# Hall_Effect_Sensor.net
KiCad netlist of a schematic drawn in EAGLE
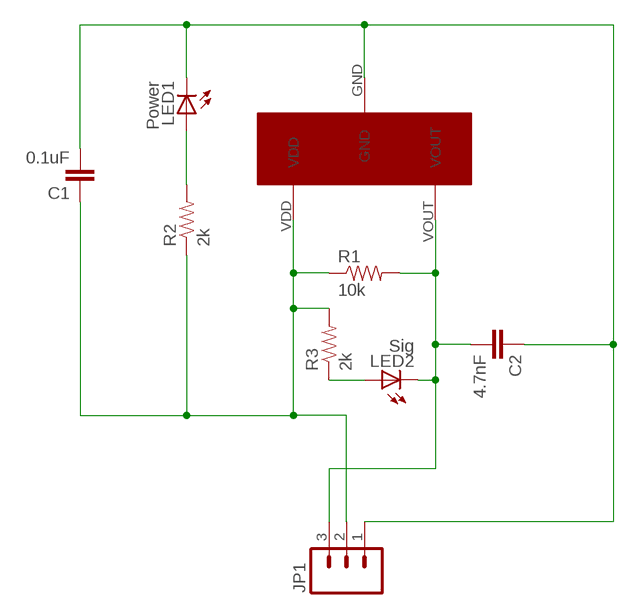
[diagram p0: schematic, sheet 1]

(export (version "E")
  (design (tool "Eeschema 10.0.6"))
  (components
    (comp (ref "C1")
      (value "0.1uF")
      (footprint "eagle-import:0603-CAP")
      (libsource (lib "eagle-import") (part "CAP0603-CAP"))
    )
    (comp (ref "C2")
      (value "4.7nF")
      (footprint "eagle-import:0603-CAP")
      (libsource (lib "eagle-import") (part "CAP0603-CAP"))
    )
    (comp (ref "JP1")
      (value "M03PTH")
      (footprint "eagle-import:1X03")
      (libsource (lib "eagle-import") (part "M03PTH"))
    )
    (comp (ref "LED1")
      (value "Power")
      (footprint "eagle-import:LED-0603")
      (libsource (lib "eagle-import") (part "LED0603"))
    )
    (comp (ref "LED2")
      (value "Sig")
      (footprint "eagle-import:LED-0603")
      (libsource (lib "eagle-import") (part "LED0603"))
    )
    (comp (ref "R1")
      (value "10k")
      (footprint "eagle-import:0603-RES")
      (libsource (lib "eagle-import") (part "RESISTOR0603-RES"))
    )
    (comp (ref "R2")
      (value "2k")
      (footprint "eagle-import:0603-RES")
      (libsource (lib "eagle-import") (part "RESISTOR0603-RES"))
    )
    (comp (ref "R3")
      (value "2k")
      (footprint "eagle-import:0603-RES")
      (libsource (lib "eagle-import") (part "RESISTOR0603-RES"))
    )
    (comp (ref "U$1")
      (value "US5881-HALL-EFFECT")
      (footprint "eagle-import:US5881-HALL-EFFECT")
      (libsource (lib "eagle-import") (part "US5881-HALL-EFFECT"))
    )
  )
  (nets
    (net (code "1") (name "Net-(C1-Pad1)") (class "Default")
      (node (ref "C1") (pin "1") (pinfunction "1_1") (pintype "passive"))
      (node (ref "JP1") (pin "2") (pinfunction "2_2") (pintype "passive"))
      (node (ref "R1") (pin "1") (pinfunction "1_1") (pintype "passive"))
      (node (ref "R2") (pin "1") (pinfunction "1_1") (pintype "passive"))
      (node (ref "R3") (pin "2") (pinfunction "2_2") (pintype "passive"))
      (node (ref "U$1") (pin "VDD") (pinfunction "VDD_VDD") (pintype "bidirectional"))
    )
    (net (code "2") (name "Net-(C1-Pad2)") (class "Default")
      (node (ref "C1") (pin "2") (pinfunction "2_2") (pintype "passive"))
      (node (ref "C2") (pin "1") (pinfunction "1_1") (pintype "passive"))
      (node (ref "JP1") (pin "1") (pinfunction "1_1") (pintype "passive"))
      (node (ref "LED1") (pin "C") (pinfunction "C_C") (pintype "passive"))
      (node (ref "U$1") (pin "GND") (pinfunction "GND_GND") (pintype "bidirectional"))
    )
    (net (code "3") (name "Net-(C2-Pad2)") (class "Default")
      (node (ref "C2") (pin "2") (pinfunction "2_2") (pintype "passive"))
      (node (ref "JP1") (pin "3") (pinfunction "3_3") (pintype "passive"))
      (node (ref "LED2") (pin "C") (pinfunction "C_C") (pintype "passive"))
      (node (ref "R1") (pin "2") (pinfunction "2_2") (pintype "passive"))
      (node (ref "U$1") (pin "VOUT") (pinfunction "VOUT_VOUT") (pintype "bidirectional"))
    )
    (net (code "4") (name "Net-(LED1-PadA)") (class "Default")
      (node (ref "LED1") (pin "A") (pinfunction "A_A") (pintype "passive"))
      (node (ref "R2") (pin "2") (pinfunction "2_2") (pintype "passive"))
    )
    (net (code "5") (name "Net-(LED2-PadA)") (class "Default")
      (node (ref "LED2") (pin "A") (pinfunction "A_A") (pintype "passive"))
      (node (ref "R3") (pin "1") (pinfunction "1_1") (pintype "passive"))
    )
  )
)
